# RasPiHAT-DISPLAY.net
KiCad netlist of a schematic drawn in Altium Designer
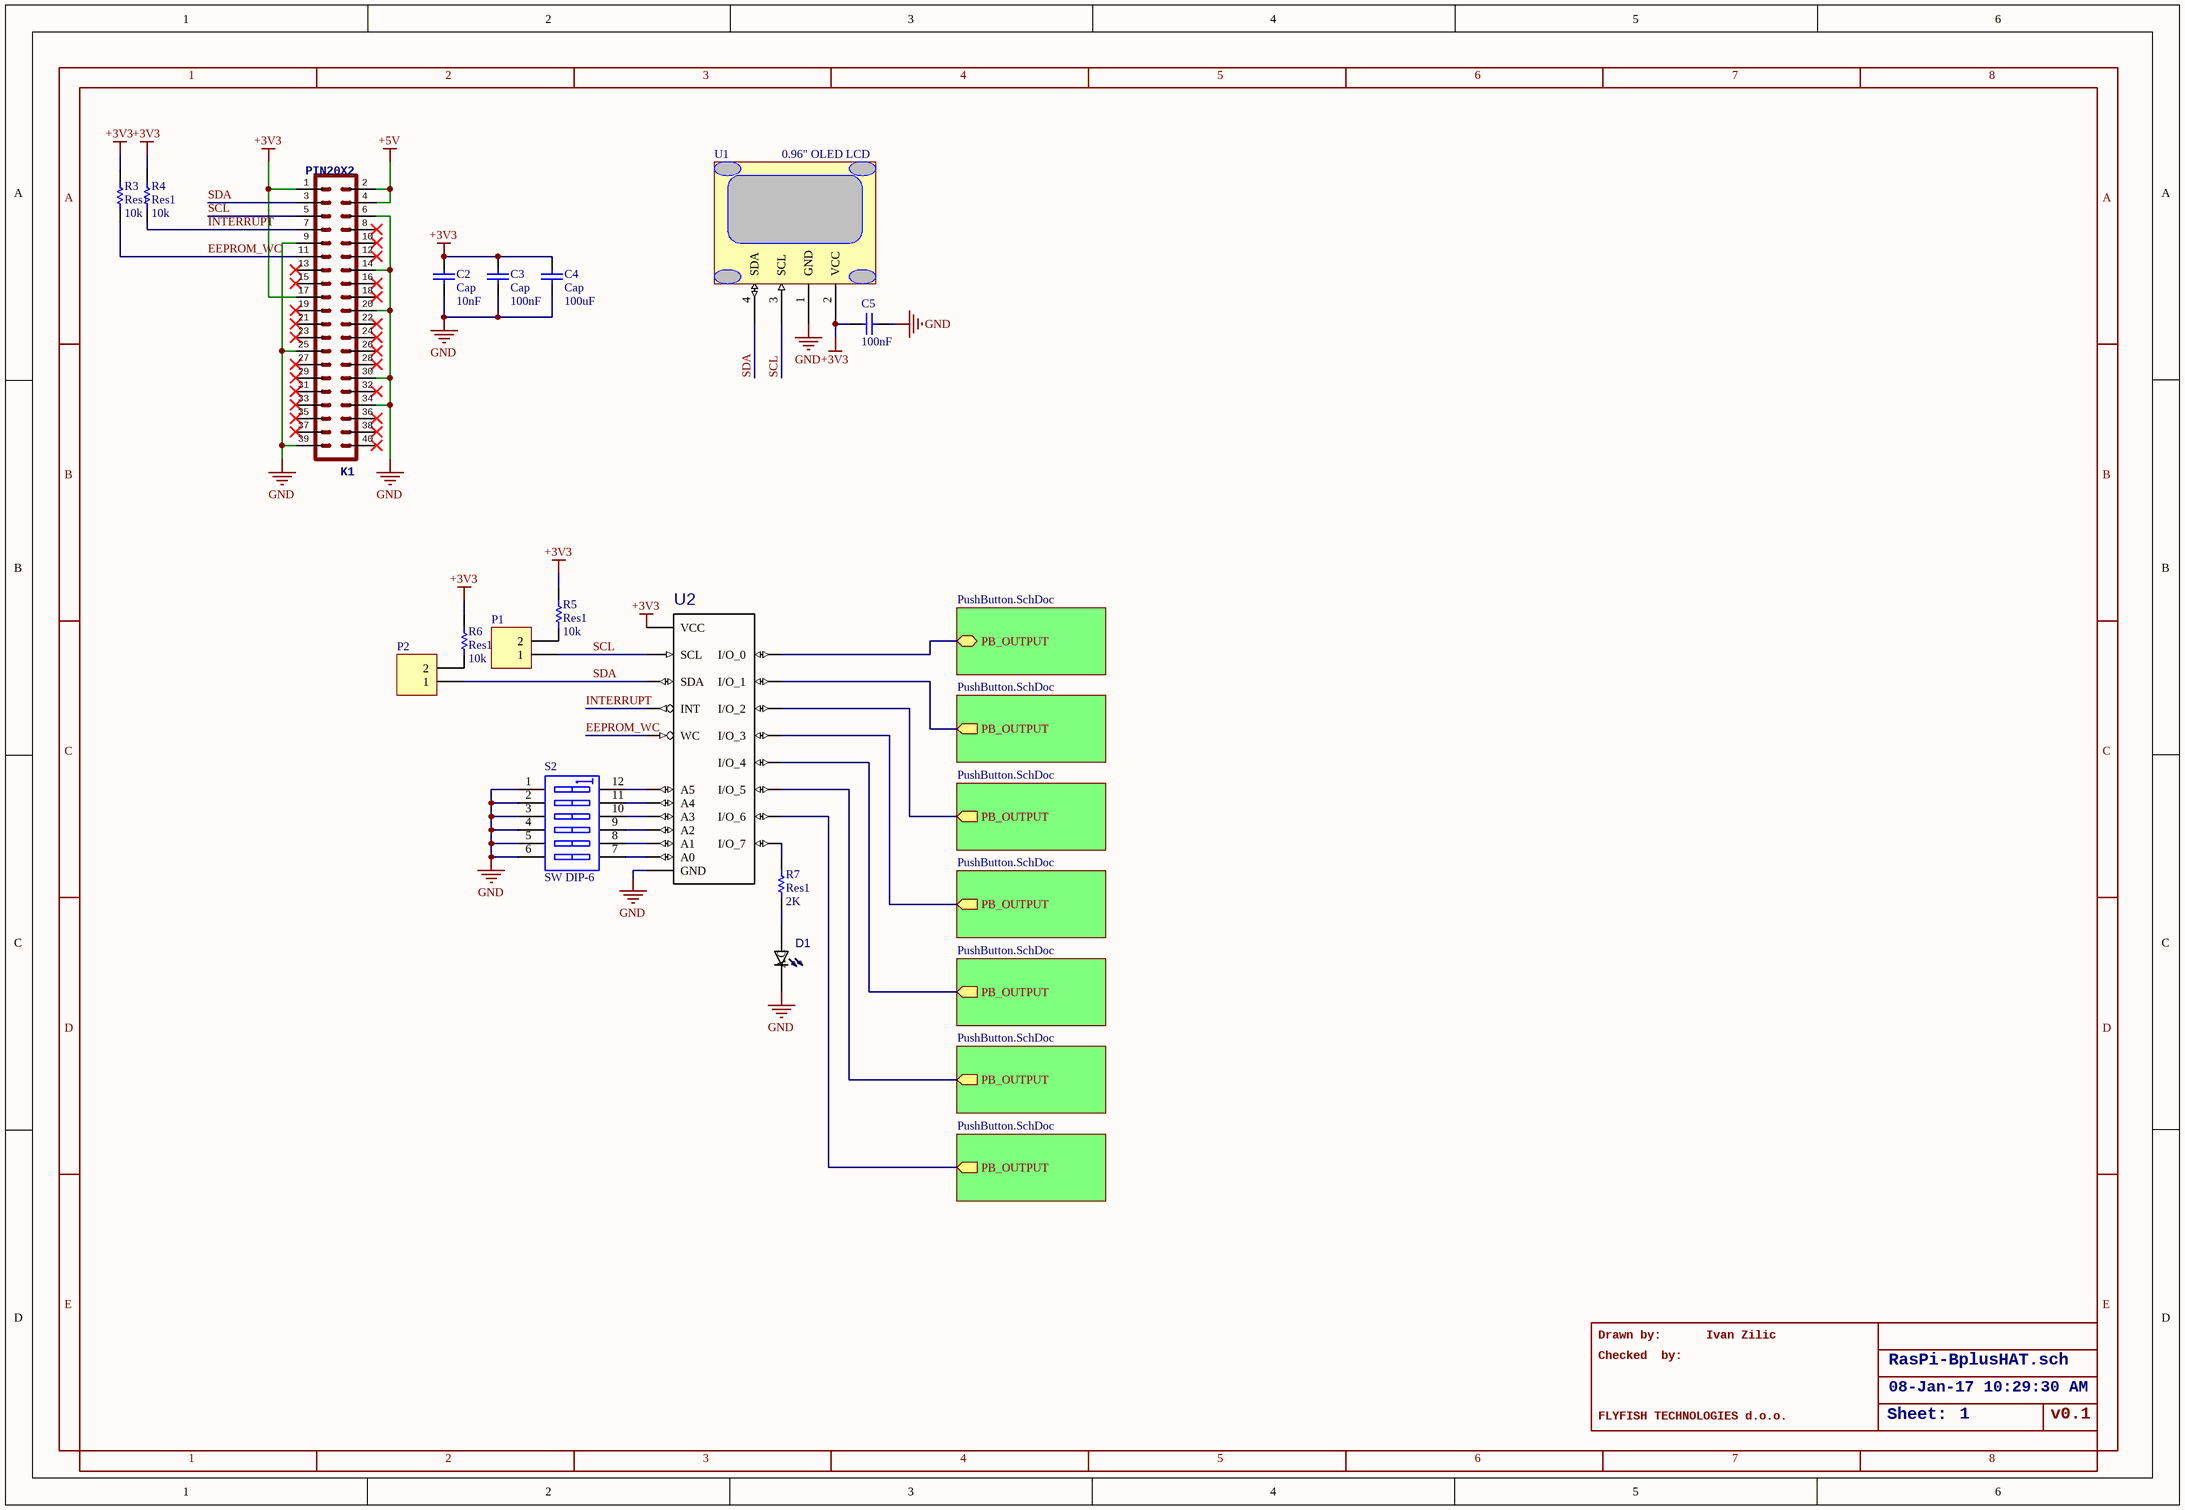
[diagram p0: RasPiHAT-DISPLAY.SchDoc]

(export (version "E")
  (design (tool "Eeschema 10.0.6"))
  (components
    (comp (ref "C2")
      (value "Cap")
      (footprint "6-0805_N")
      (description "Capacitor")
      (fields (field (name "ALTIUM_VALUE") "10nF") (field (name "PUBLISHER") "Altium Limited"))
      (libsource (lib "Miscellaneous Devices") (part "Cap"))
    )
    (comp (ref "C3")
      (value "Cap")
      (footprint "6-0805_N")
      (description "Capacitor")
      (fields (field (name "ALTIUM_VALUE") "100nF") (field (name "PUBLISHER") "Altium Limited"))
      (libsource (lib "Miscellaneous Devices") (part "Cap"))
    )
    (comp (ref "C4")
      (value "Cap")
      (footprint "6-0805_N")
      (description "Capacitor")
      (fields (field (name "ALTIUM_VALUE") "100uF") (field (name "PUBLISHER") "Altium Limited"))
      (libsource (lib "Miscellaneous Devices") (part "Cap"))
    )
    (comp (ref "C5")
      (value "100nF")
      (footprint "6-0805_N")
      (description "Capacitor")
      (fields (field (name "Comment") "0805"))
      (libsource (lib "Miscellaneous Devices") (part "Cap Semi"))
    )
    (comp (ref "D1")
      (value "0805_LED")
      (footprint "LEDSC200X125X70-2N_598-8160-107F(Primary)")
      (description "LED, SMD; 0805; Yellow-Green; Water Clear Lens; 40mcd; 570/575nm")
      (fields (field (name "MP") "598-8160-107F") (field (name "MF") "Dialight"))
      (libsource (lib "0805_LED") (part "598-8160-107F"))
    )
    (comp (ref "K1")
      (value "PIN20X2")
      (footprint "HDR2X20")
      (fields (field (name ">VALUE") "PIN20X2") (field (name ">NAME") "K1"))
      (libsource (lib "FLYFISH") (part "PIN20X2"))
    )
    (comp (ref "P1")
      (value "Header 2")
      (footprint "HDR1X2")
      (description "Header, 2-Pin")
      (fields (field (name "PUBLISHER") "Altium Limited"))
      (libsource (lib "Miscellaneous Connectors") (part "Header 2"))
    )
    (comp (ref "P2")
      (value "Header 2")
      (footprint "HDR1X2")
      (description "Header, 2-Pin")
      (fields (field (name "PUBLISHER") "Altium Limited"))
      (libsource (lib "Miscellaneous Connectors") (part "Header 2"))
    )
    (comp (ref "R3")
      (value "Res1")
      (footprint "6-0805_N")
      (description "Resistor")
      (fields (field (name "ALTIUM_VALUE") "10k") (field (name "PUBLISHER") "Altium Limited"))
      (libsource (lib "Miscellaneous Devices") (part "Res1"))
    )
    (comp (ref "R4")
      (value "Res1")
      (footprint "6-0805_N")
      (description "Resistor")
      (fields (field (name "ALTIUM_VALUE") "10k") (field (name "PUBLISHER") "Altium Limited"))
      (libsource (lib "Miscellaneous Devices") (part "Res1"))
    )
    (comp (ref "R5")
      (value "Res1")
      (footprint "6-0805_N")
      (description "Resistor")
      (fields (field (name "ALTIUM_VALUE") "10k") (field (name "PUBLISHER") "Altium Limited"))
      (libsource (lib "Miscellaneous Devices") (part "Res1"))
    )
    (comp (ref "R6")
      (value "Res1")
      (footprint "6-0805_N")
      (description "Resistor")
      (fields (field (name "ALTIUM_VALUE") "10k") (field (name "PUBLISHER") "Altium Limited"))
      (libsource (lib "Miscellaneous Devices") (part "Res1"))
    )
    (comp (ref "R7")
      (value "Res1")
      (footprint "6-0805_N")
      (description "Resistor")
      (fields (field (name "ALTIUM_VALUE") "2K") (field (name "PUBLISHER") "Altium Limited"))
      (libsource (lib "Miscellaneous Devices") (part "Res1"))
    )
    (comp (ref "S2")
      (value "SW DIP-6")
      (footprint "DIP-12/SW")
      (description "DIP Switch, 6 Position, SPST")
      (fields (field (name "PUBLISHER") "Altium Limited"))
      (libsource (lib "Miscellaneous Devices") (part "SW DIP-6"))
    )
    (comp (ref "U1")
      (value "0.96\" OLED LCD")
      (footprint "0.96 OLED LCD")
      (libsource (lib "0.96OLEDLCD") (part "0.96{dblquote} OLED LCD"))
    )
    (comp (ref "U2")
      (value "PCA9501")
      (footprint "TSSOP20")
      (fields (field (name "MF") "NXP Semiconductors"))
      (libsource (lib "PCA9501") (part "PCA9501"))
    )
  )
  (nets
    (net (code "1") (name "+3V3") (class "Default")
      (node (ref "C2") (pin "2") (pinfunction "2_2") (pintype "passive"))
      (node (ref "C3") (pin "2") (pinfunction "2_2") (pintype "passive"))
      (node (ref "C4") (pin "2") (pinfunction "2_2") (pintype "passive"))
      (node (ref "C5") (pin "1") (pinfunction "1_1") (pintype "passive"))
      (node (ref "K1") (pin "1") (pinfunction "1_1") (pintype "passive"))
      (node (ref "K1") (pin "17") (pinfunction "17_17") (pintype "passive"))
      (node (ref "R3") (pin "1") (pinfunction "1_1") (pintype "passive"))
      (node (ref "R4") (pin "1") (pinfunction "1_1") (pintype "passive"))
      (node (ref "R5") (pin "1") (pinfunction "1_1") (pintype "passive"))
      (node (ref "R6") (pin "1") (pinfunction "1_1") (pintype "passive"))
      (node (ref "U1") (pin "2") (pinfunction "VCC_2") (pintype "power_in"))
      (node (ref "U2") (pin "20") (pinfunction "VCC_20") (pintype "power_in"))
    )
    (net (code "2") (name "+5V") (class "Default")
      (node (ref "K1") (pin "2") (pinfunction "2_2") (pintype "passive"))
      (node (ref "K1") (pin "4") (pinfunction "4_4") (pintype "passive"))
    )
    (net (code "3") (name "/EEPROM_WC") (class "Default")
      (node (ref "K1") (pin "11") (pinfunction "11_11") (pintype "passive"))
      (node (ref "R3") (pin "2") (pinfunction "2_2") (pintype "passive"))
      (node (ref "U2") (pin "17") (pinfunction "WC_17") (pintype "input"))
    )
    (net (code "4") (name "/INTERRUPT") (class "Default")
      (node (ref "K1") (pin "7") (pinfunction "7_7") (pintype "passive"))
      (node (ref "R4") (pin "2") (pinfunction "2_2") (pintype "passive"))
      (node (ref "U2") (pin "8") (pinfunction "INT_8") (pintype "output"))
    )
    (net (code "5") (name "/PB_OUTPUT") (class "Default")
      (node (ref "U2") (pin "4") (pinfunction "I/O_0_4") (pintype "bidirectional"))
    )
    (net (code "6") (name "/PB_OUTPUT_1") (class "Default")
      (node (ref "U2") (pin "15") (pinfunction "I/O_6_15") (pintype "bidirectional"))
    )
    (net (code "7") (name "/PB_OUTPUT_2") (class "Default")
      (node (ref "U2") (pin "14") (pinfunction "I/O_5_14") (pintype "bidirectional"))
    )
    (net (code "8") (name "/PB_OUTPUT_3") (class "Default")
      (node (ref "U2") (pin "13") (pinfunction "I/O_4_13") (pintype "bidirectional"))
    )
    (net (code "9") (name "/PB_OUTPUT_4") (class "Default")
      (node (ref "U2") (pin "7") (pinfunction "I/O_3_7") (pintype "bidirectional"))
    )
    (net (code "10") (name "/PB_OUTPUT_5") (class "Default")
      (node (ref "U2") (pin "6") (pinfunction "I/O_2_6") (pintype "bidirectional"))
    )
    (net (code "11") (name "/PB_OUTPUT_6") (class "Default")
      (node (ref "U2") (pin "5") (pinfunction "I/O_1_5") (pintype "bidirectional"))
    )
    (net (code "12") (name "/SCL") (class "Default")
      (node (ref "K1") (pin "5") (pinfunction "5_5") (pintype "passive"))
      (node (ref "P1") (pin "1") (pinfunction "1_1") (pintype "passive"))
      (node (ref "U1") (pin "3") (pinfunction "SCL_3") (pintype "input"))
      (node (ref "U2") (pin "18") (pinfunction "SCL_18") (pintype "input"))
    )
    (net (code "13") (name "/SDA") (class "Default")
      (node (ref "K1") (pin "3") (pinfunction "3_3") (pintype "passive"))
      (node (ref "P2") (pin "1") (pinfunction "1_1") (pintype "passive"))
      (node (ref "U1") (pin "4") (pinfunction "SDA_4") (pintype "bidirectional"))
      (node (ref "U2") (pin "19") (pinfunction "SDA_19") (pintype "bidirectional"))
    )
    (net (code "14") (name "GND") (class "Default")
      (node (ref "C2") (pin "1") (pinfunction "1_1") (pintype "passive"))
      (node (ref "C3") (pin "1") (pinfunction "1_1") (pintype "passive"))
      (node (ref "C4") (pin "1") (pinfunction "1_1") (pintype "passive"))
      (node (ref "C5") (pin "2") (pinfunction "2_2") (pintype "passive"))
      (node (ref "D1") (pin "C") (pinfunction "C_C") (pintype "passive"))
      (node (ref "K1") (pin "14") (pinfunction "14_14") (pintype "passive"))
      (node (ref "K1") (pin "20") (pinfunction "20_20") (pintype "passive"))
      (node (ref "K1") (pin "25") (pinfunction "25_25") (pintype "passive"))
      (node (ref "K1") (pin "30") (pinfunction "30_30") (pintype "passive"))
      (node (ref "K1") (pin "34") (pinfunction "34_34") (pintype "passive"))
      (node (ref "K1") (pin "39") (pinfunction "39_39") (pintype "passive"))
      (node (ref "K1") (pin "6") (pinfunction "6_6") (pintype "passive"))
      (node (ref "K1") (pin "9") (pinfunction "9_9") (pintype "passive"))
      (node (ref "S2") (pin "1") (pinfunction "A1_1") (pintype "passive"))
      (node (ref "S2") (pin "2") (pinfunction "A2_2") (pintype "passive"))
      (node (ref "S2") (pin "3") (pinfunction "A3_3") (pintype "passive"))
      (node (ref "S2") (pin "4") (pinfunction "A4_4") (pintype "passive"))
      (node (ref "S2") (pin "5") (pinfunction "A5_5") (pintype "passive"))
      (node (ref "S2") (pin "6") (pinfunction "A6_6") (pintype "passive"))
      (node (ref "U1") (pin "1") (pinfunction "GND_1") (pintype "power_in"))
      (node (ref "U2") (pin "10") (pinfunction "GND_10") (pintype "power_in"))
    )
    (net (code "15") (name "Net-(D1-PadA)") (class "Default")
      (node (ref "D1") (pin "A") (pinfunction "A_A") (pintype "passive"))
      (node (ref "R7") (pin "2") (pinfunction "2_2") (pintype "passive"))
    )
    (net (code "16") (name "Net-(P1-Pad2)") (class "Default")
      (node (ref "P1") (pin "2") (pinfunction "2_2") (pintype "passive"))
      (node (ref "R5") (pin "2") (pinfunction "2_2") (pintype "passive"))
    )
    (net (code "17") (name "Net-(P2-Pad2)") (class "Default")
      (node (ref "P2") (pin "2") (pinfunction "2_2") (pintype "passive"))
      (node (ref "R6") (pin "2") (pinfunction "2_2") (pintype "passive"))
    )
    (net (code "18") (name "Net-(S2-B1)") (class "Default")
      (node (ref "S2") (pin "12") (pinfunction "B1_12") (pintype "passive"))
      (node (ref "U2") (pin "9") (pinfunction "A5_9") (pintype "bidirectional"))
    )
    (net (code "19") (name "Net-(S2-B2)") (class "Default")
      (node (ref "S2") (pin "11") (pinfunction "B2_11") (pintype "passive"))
      (node (ref "U2") (pin "11") (pinfunction "A4_11") (pintype "bidirectional"))
    )
    (net (code "20") (name "Net-(S2-B3)") (class "Default")
      (node (ref "S2") (pin "10") (pinfunction "B3_10") (pintype "passive"))
      (node (ref "U2") (pin "12") (pinfunction "A3_12") (pintype "bidirectional"))
    )
    (net (code "21") (name "Net-(S2-B4)") (class "Default")
      (node (ref "S2") (pin "9") (pinfunction "B4_9") (pintype "passive"))
      (node (ref "U2") (pin "3") (pinfunction "A2_3") (pintype "bidirectional"))
    )
    (net (code "22") (name "Net-(S2-B5)") (class "Default")
      (node (ref "S2") (pin "8") (pinfunction "B5_8") (pintype "passive"))
      (node (ref "U2") (pin "2") (pinfunction "A1_2") (pintype "bidirectional"))
    )
    (net (code "23") (name "Net-(S2-B6)") (class "Default")
      (node (ref "S2") (pin "7") (pinfunction "B6_7") (pintype "passive"))
      (node (ref "U2") (pin "1") (pinfunction "A0_1") (pintype "bidirectional"))
    )
    (net (code "24") (name "Net-(U2-I{slash}O_7)") (class "Default")
      (node (ref "R7") (pin "1") (pinfunction "1_1") (pintype "passive"))
      (node (ref "U2") (pin "16") (pinfunction "I/O_7_16") (pintype "bidirectional"))
    )
    (net (code "25") (name "unconnected-(K1-Pad8)") (class "Default")
      (node (ref "K1") (pin "8") (pinfunction "8_8") (pintype "passive+no_connect"))
    )
    (net (code "26") (name "unconnected-(K1-Pad10)") (class "Default")
      (node (ref "K1") (pin "10") (pinfunction "10_10") (pintype "passive+no_connect"))
    )
    (net (code "27") (name "unconnected-(K1-Pad12)") (class "Default")
      (node (ref "K1") (pin "12") (pinfunction "12_12") (pintype "passive+no_connect"))
    )
    (net (code "28") (name "unconnected-(K1-Pad13)") (class "Default")
      (node (ref "K1") (pin "13") (pinfunction "13_13") (pintype "passive+no_connect"))
    )
    (net (code "29") (name "unconnected-(K1-Pad15)") (class "Default")
      (node (ref "K1") (pin "15") (pinfunction "15_15") (pintype "passive+no_connect"))
    )
    (net (code "30") (name "unconnected-(K1-Pad16)") (class "Default")
      (node (ref "K1") (pin "16") (pinfunction "16_16") (pintype "passive+no_connect"))
    )
    (net (code "31") (name "unconnected-(K1-Pad18)") (class "Default")
      (node (ref "K1") (pin "18") (pinfunction "18_18") (pintype "passive+no_connect"))
    )
    (net (code "32") (name "unconnected-(K1-Pad19)") (class "Default")
      (node (ref "K1") (pin "19") (pinfunction "19_19") (pintype "passive+no_connect"))
    )
    (net (code "33") (name "unconnected-(K1-Pad21)") (class "Default")
      (node (ref "K1") (pin "21") (pinfunction "21_21") (pintype "passive+no_connect"))
    )
    (net (code "34") (name "unconnected-(K1-Pad22)") (class "Default")
      (node (ref "K1") (pin "22") (pinfunction "22_22") (pintype "passive+no_connect"))
    )
    (net (code "35") (name "unconnected-(K1-Pad23)") (class "Default")
      (node (ref "K1") (pin "23") (pinfunction "23_23") (pintype "passive+no_connect"))
    )
    (net (code "36") (name "unconnected-(K1-Pad24)") (class "Default")
      (node (ref "K1") (pin "24") (pinfunction "24_24") (pintype "passive+no_connect"))
    )
    (net (code "37") (name "unconnected-(K1-Pad26)") (class "Default")
      (node (ref "K1") (pin "26") (pinfunction "26_26") (pintype "passive+no_connect"))
    )
    (net (code "38") (name "unconnected-(K1-Pad27)") (class "Default")
      (node (ref "K1") (pin "27") (pinfunction "27_27") (pintype "passive+no_connect"))
    )
    (net (code "39") (name "unconnected-(K1-Pad28)") (class "Default")
      (node (ref "K1") (pin "28") (pinfunction "28_28") (pintype "passive+no_connect"))
    )
    (net (code "40") (name "unconnected-(K1-Pad29)") (class "Default")
      (node (ref "K1") (pin "29") (pinfunction "29_29") (pintype "passive+no_connect"))
    )
    (net (code "41") (name "unconnected-(K1-Pad31)") (class "Default")
      (node (ref "K1") (pin "31") (pinfunction "31_31") (pintype "passive+no_connect"))
    )
    (net (code "42") (name "unconnected-(K1-Pad32)") (class "Default")
      (node (ref "K1") (pin "32") (pinfunction "32_32") (pintype "passive+no_connect"))
    )
    (net (code "43") (name "unconnected-(K1-Pad33)") (class "Default")
      (node (ref "K1") (pin "33") (pinfunction "33_33") (pintype "passive+no_connect"))
    )
    (net (code "44") (name "unconnected-(K1-Pad35)") (class "Default")
      (node (ref "K1") (pin "35") (pinfunction "35_35") (pintype "passive+no_connect"))
    )
    (net (code "45") (name "unconnected-(K1-Pad36)") (class "Default")
      (node (ref "K1") (pin "36") (pinfunction "36_36") (pintype "passive+no_connect"))
    )
    (net (code "46") (name "unconnected-(K1-Pad37)") (class "Default")
      (node (ref "K1") (pin "37") (pinfunction "37_37") (pintype "passive+no_connect"))
    )
    (net (code "47") (name "unconnected-(K1-Pad38)") (class "Default")
      (node (ref "K1") (pin "38") (pinfunction "38_38") (pintype "passive+no_connect"))
    )
    (net (code "48") (name "unconnected-(K1-Pad40)") (class "Default")
      (node (ref "K1") (pin "40") (pinfunction "40_40") (pintype "passive+no_connect"))
    )
  )
)
